# rapidshark-forward-breakout-mk-1_0.net
KiCad netlist of a schematic drawn in EAGLE
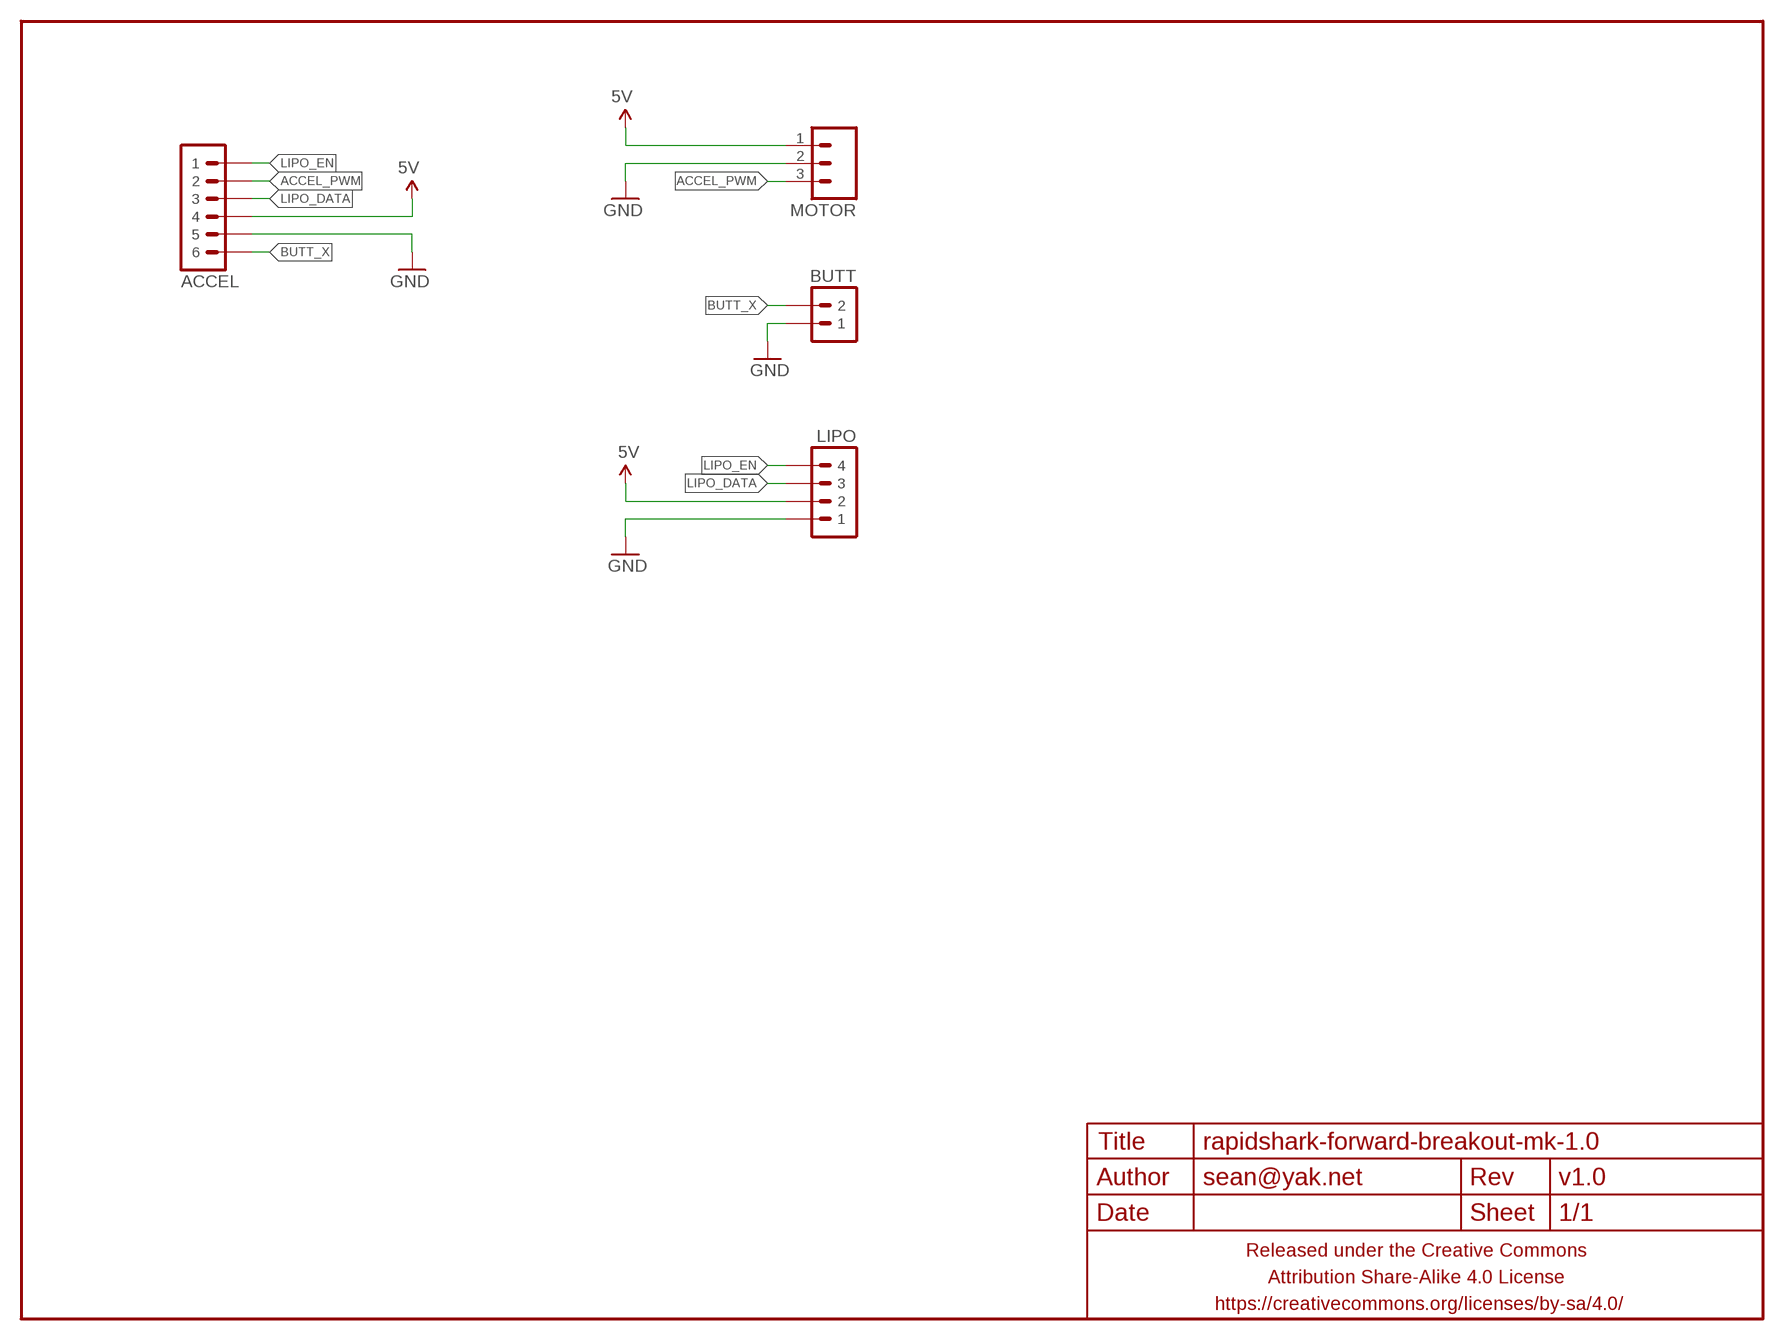
[diagram p0: schematic, sheet 1]

(export (version "E")
  (design (tool "Eeschema 10.0.6"))
  (components
    (comp (ref "ACCEL")
      (value "M06JST-PH-PTH-VERT")
      (footprint "eagle-import:JST-6-PH-VERT-PTH")
      (libsource (lib "eagle-import") (part "M06JST-PH-PTH-VERT"))
    )
    (comp (ref "BUTT")
      (value "M02JST-PTH-VERT")
      (footprint "eagle-import:JST-2-PH-VERT-PTH")
      (libsource (lib "eagle-import") (part "M02JST-PTH-VERT"))
    )
    (comp (ref "FRAME1")
      (value "FRAME-LETTERNO_PACKAGE")
      (footprint "eagle-import:DUMMY")
      (fields (field (name "DESIGNER") "sean@yak.net") (field (name "VERSION") "v1.0"))
      (libsource (lib "eagle-import") (part "FRAME-LETTERNO_PACKAGE"))
    )
    (comp (ref "LIPO")
      (value "M04JST-PTH-VERT")
      (footprint "eagle-import:JST-4-PH-VERT-PTH")
      (libsource (lib "eagle-import") (part "M04JST-PTH-VERT"))
    )
    (comp (ref "MOTOR")
      (value "M03JST-PTH-VERT")
      (footprint "eagle-import:JST-3-PH-VERT-PTH")
      (libsource (lib "eagle-import") (part "M03JST-PTH-VERT"))
    )
  )
  (nets
    (net (code "1") (name "5V") (class "Default")
      (node (ref "ACCEL") (pin "4") (pinfunction "4_4") (pintype "passive"))
      (node (ref "LIPO") (pin "2") (pinfunction "2_2") (pintype "passive"))
      (node (ref "MOTOR") (pin "1") (pinfunction "1_1") (pintype "passive"))
    )
    (net (code "2") (name "ACCEL_PWM") (class "Default")
      (node (ref "ACCEL") (pin "2") (pinfunction "2_2") (pintype "passive"))
      (node (ref "MOTOR") (pin "3") (pinfunction "3_3") (pintype "passive"))
    )
    (net (code "3") (name "BUTT_X") (class "Default")
      (node (ref "ACCEL") (pin "6") (pinfunction "6_6") (pintype "passive"))
      (node (ref "BUTT") (pin "2") (pinfunction "2_2") (pintype "passive"))
    )
    (net (code "4") (name "GND") (class "Default")
      (node (ref "ACCEL") (pin "5") (pinfunction "5_5") (pintype "passive"))
      (node (ref "BUTT") (pin "1") (pinfunction "1_1") (pintype "passive"))
      (node (ref "LIPO") (pin "1") (pinfunction "1_1") (pintype "passive"))
      (node (ref "MOTOR") (pin "2") (pinfunction "2_2") (pintype "passive"))
    )
    (net (code "5") (name "LIPO_DATA") (class "Default")
      (node (ref "ACCEL") (pin "3") (pinfunction "3_3") (pintype "passive"))
      (node (ref "LIPO") (pin "3") (pinfunction "3_3") (pintype "passive"))
    )
    (net (code "6") (name "LIPO_EN") (class "Default")
      (node (ref "ACCEL") (pin "1") (pinfunction "1_1") (pintype "passive"))
      (node (ref "LIPO") (pin "4") (pinfunction "4_4") (pintype "passive"))
    )
  )
)
